# pwm_driver.net
KiCad netlist of a schematic drawn in Altium Designer
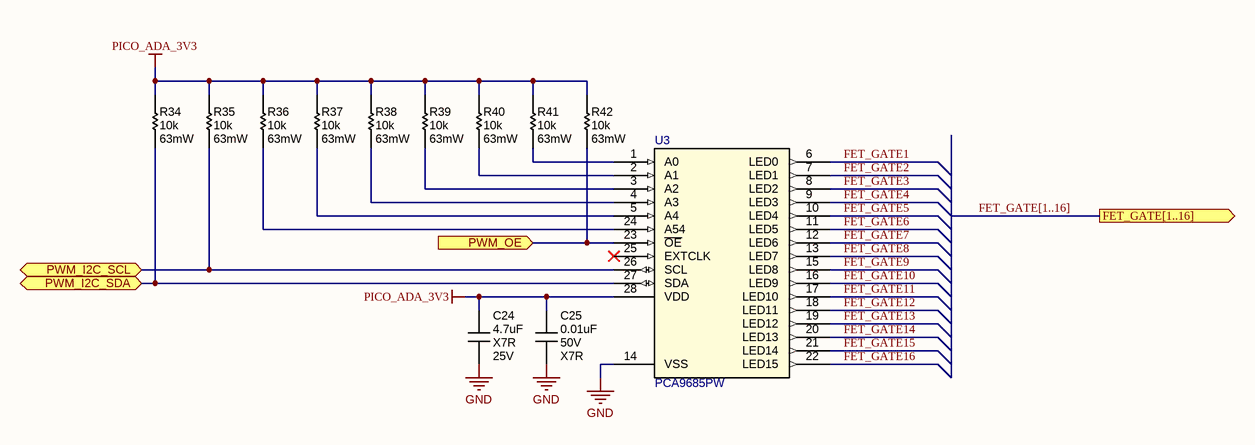
[diagram p0: pwm_driver.SchDoc]

(export (version "E")
  (design (tool "Eeschema 10.0.6"))
  (components
    (comp (ref "C24")
      (value "4.7uF")
      (footprint "CAPC2012X14N")
      (description "CAP CER 4.7UF 25V X7R 0805")
      (fields
        (field (name "MFR") "TDK Corporation")
        (field (name "TOLERANCE") "10%")
        (field (name "TEMP COEFF") "X7R")
        (field (name "VOLTAGE RATING") "25V")
      )
      (libsource (lib "General_Library") (part "CMP-004-0011"))
    )
    (comp (ref "C25")
      (value "0.01uF")
      (footprint "CAPC1005X06N")
      (description "CAP CER SMD 0.01UF 50V X7R 0402")
      (fields
        (field (name "TOLERANCE") "10%")
        (field (name "MFR") "Murata Electronics")
        (field (name "VOLTAGE RATING") "50V")
        (field (name "TEMP COEFF") "X7R")
      )
      (libsource (lib "General_Library") (part "CMP-004-0077"))
    )
    (comp (ref "R34")
      (value "10k")
      (footprint "RESC1005X04N")
      (description "RES SMD 10K OHM 0.5% 1/16W 0402")
      (fields
        (field (name "MFR") "Panasonic Electronic Components")
        (field (name "TOLERANCE") "0.5%")
        (field (name "WATTAGE") "63mW")
      )
      (libsource (lib "General_Library") (part "CMP-025-0026"))
    )
    (comp (ref "R35")
      (value "10k")
      (footprint "RESC1005X04N")
      (description "RES SMD 10K OHM 0.5% 1/16W 0402")
      (fields
        (field (name "MFR") "Panasonic Electronic Components")
        (field (name "TOLERANCE") "0.5%")
        (field (name "WATTAGE") "63mW")
      )
      (libsource (lib "General_Library") (part "CMP-025-0026"))
    )
    (comp (ref "R36")
      (value "10k")
      (footprint "RESC1005X04N")
      (description "RES SMD 10K OHM 0.5% 1/16W 0402")
      (fields
        (field (name "MFR") "Panasonic Electronic Components")
        (field (name "TOLERANCE") "0.5%")
        (field (name "WATTAGE") "63mW")
      )
      (libsource (lib "General_Library") (part "CMP-025-0026"))
    )
    (comp (ref "R37")
      (value "10k")
      (footprint "RESC1005X04N")
      (description "RES SMD 10K OHM 0.5% 1/16W 0402")
      (fields
        (field (name "MFR") "Panasonic Electronic Components")
        (field (name "TOLERANCE") "0.5%")
        (field (name "WATTAGE") "63mW")
      )
      (libsource (lib "General_Library") (part "CMP-025-0026"))
    )
    (comp (ref "R38")
      (value "10k")
      (footprint "RESC1005X04N")
      (description "RES SMD 10K OHM 0.5% 1/16W 0402")
      (fields
        (field (name "MFR") "Panasonic Electronic Components")
        (field (name "TOLERANCE") "0.5%")
        (field (name "WATTAGE") "63mW")
      )
      (libsource (lib "General_Library") (part "CMP-025-0026"))
    )
    (comp (ref "R39")
      (value "10k")
      (footprint "RESC1005X04N")
      (description "RES SMD 10K OHM 0.5% 1/16W 0402")
      (fields
        (field (name "MFR") "Panasonic Electronic Components")
        (field (name "TOLERANCE") "0.5%")
        (field (name "WATTAGE") "63mW")
      )
      (libsource (lib "General_Library") (part "CMP-025-0026"))
    )
    (comp (ref "R40")
      (value "10k")
      (footprint "RESC1005X04N")
      (description "RES SMD 10K OHM 0.5% 1/16W 0402")
      (fields
        (field (name "MFR") "Panasonic Electronic Components")
        (field (name "TOLERANCE") "0.5%")
        (field (name "WATTAGE") "63mW")
      )
      (libsource (lib "General_Library") (part "CMP-025-0026"))
    )
    (comp (ref "R41")
      (value "10k")
      (footprint "RESC1005X04N")
      (description "RES SMD 10K OHM 0.5% 1/16W 0402")
      (fields
        (field (name "MFR") "Panasonic Electronic Components")
        (field (name "TOLERANCE") "0.5%")
        (field (name "WATTAGE") "63mW")
      )
      (libsource (lib "General_Library") (part "CMP-025-0026"))
    )
    (comp (ref "R42")
      (value "10k")
      (footprint "RESC1005X04N")
      (description "RES SMD 10K OHM 0.5% 1/16W 0402")
      (fields
        (field (name "MFR") "Panasonic Electronic Components")
        (field (name "TOLERANCE") "0.5%")
        (field (name "WATTAGE") "63mW")
      )
      (libsource (lib "General_Library") (part "CMP-025-0026"))
    )
    (comp (ref "U3")
      (value "PCA9685PW")
      (footprint "SOP65P640X120-29N")
      (description "IC LED DRVR LIN PWM 25MA 28TSSOP")
      (fields (field (name "MFR") "NXP"))
      (libsource (lib "General_Library") (part "CMP-017-0112"))
    )
  )
  (nets
    (net (code "1") (name "/FET_GATE1") (class "Default")
      (node (ref "U3") (pin "6") (pinfunction "LED0_6") (pintype "output"))
    )
    (net (code "2") (name "/FET_GATE2") (class "Default")
      (node (ref "U3") (pin "7") (pinfunction "LED1_7") (pintype "output"))
    )
    (net (code "3") (name "/FET_GATE3") (class "Default")
      (node (ref "U3") (pin "8") (pinfunction "LED2_8") (pintype "output"))
    )
    (net (code "4") (name "/FET_GATE4") (class "Default")
      (node (ref "U3") (pin "9") (pinfunction "LED3_9") (pintype "output"))
    )
    (net (code "5") (name "/FET_GATE5") (class "Default")
      (node (ref "U3") (pin "10") (pinfunction "LED4_10") (pintype "output"))
    )
    (net (code "6") (name "/FET_GATE6") (class "Default")
      (node (ref "U3") (pin "11") (pinfunction "LED5_11") (pintype "output"))
    )
    (net (code "7") (name "/FET_GATE7") (class "Default")
      (node (ref "U3") (pin "12") (pinfunction "LED6_12") (pintype "output"))
    )
    (net (code "8") (name "/FET_GATE8") (class "Default")
      (node (ref "U3") (pin "13") (pinfunction "LED7_13") (pintype "output"))
    )
    (net (code "9") (name "/FET_GATE9") (class "Default")
      (node (ref "U3") (pin "15") (pinfunction "LED8_15") (pintype "output"))
    )
    (net (code "10") (name "/FET_GATE10") (class "Default")
      (node (ref "U3") (pin "16") (pinfunction "LED9_16") (pintype "output"))
    )
    (net (code "11") (name "/FET_GATE11") (class "Default")
      (node (ref "U3") (pin "17") (pinfunction "LED10_17") (pintype "output"))
    )
    (net (code "12") (name "/FET_GATE12") (class "Default")
      (node (ref "U3") (pin "18") (pinfunction "LED11_18") (pintype "output"))
    )
    (net (code "13") (name "/FET_GATE13") (class "Default")
      (node (ref "U3") (pin "19") (pinfunction "LED12_19") (pintype "output"))
    )
    (net (code "14") (name "/FET_GATE14") (class "Default")
      (node (ref "U3") (pin "20") (pinfunction "LED13_20") (pintype "output"))
    )
    (net (code "15") (name "/FET_GATE15") (class "Default")
      (node (ref "U3") (pin "21") (pinfunction "LED14_21") (pintype "output"))
    )
    (net (code "16") (name "/FET_GATE16") (class "Default")
      (node (ref "U3") (pin "22") (pinfunction "LED15_22") (pintype "output"))
    )
    (net (code "18") (name "/PWM_I2C_SCL") (class "Default")
      (node (ref "R35") (pin "1") (pinfunction "1_1") (pintype "passive"))
      (node (ref "U3") (pin "26") (pinfunction "SCL_26") (pintype "bidirectional"))
    )
    (net (code "19") (name "/PWM_I2C_SDA") (class "Default")
      (node (ref "R34") (pin "1") (pinfunction "1_1") (pintype "passive"))
      (node (ref "U3") (pin "27") (pinfunction "SDA_27") (pintype "bidirectional"))
    )
    (net (code "20") (name "/PWM_OE") (class "Default")
      (node (ref "R42") (pin "1") (pinfunction "1_1") (pintype "passive"))
      (node (ref "U3") (pin "23") (pinfunction "~{OE}_23") (pintype "input"))
    )
    (net (code "21") (name "GND") (class "Default")
      (node (ref "C24") (pin "2") (pinfunction "2_2") (pintype "passive"))
      (node (ref "C25") (pin "2") (pinfunction "2_2") (pintype "passive"))
      (node (ref "U3") (pin "14") (pinfunction "VSS_14") (pintype "power_in"))
    )
    (net (code "22") (name "Net-(U3-A0)") (class "Default")
      (node (ref "R41") (pin "1") (pinfunction "1_1") (pintype "passive"))
      (node (ref "U3") (pin "1") (pinfunction "A0_1") (pintype "input"))
    )
    (net (code "23") (name "Net-(U3-A1)") (class "Default")
      (node (ref "R40") (pin "1") (pinfunction "1_1") (pintype "passive"))
      (node (ref "U3") (pin "2") (pinfunction "A1_2") (pintype "input"))
    )
    (net (code "24") (name "Net-(U3-A2)") (class "Default")
      (node (ref "R39") (pin "1") (pinfunction "1_1") (pintype "passive"))
      (node (ref "U3") (pin "3") (pinfunction "A2_3") (pintype "input"))
    )
    (net (code "25") (name "Net-(U3-A3)") (class "Default")
      (node (ref "R38") (pin "1") (pinfunction "1_1") (pintype "passive"))
      (node (ref "U3") (pin "4") (pinfunction "A3_4") (pintype "input"))
    )
    (net (code "26") (name "Net-(U3-A4)") (class "Default")
      (node (ref "R37") (pin "1") (pinfunction "1_1") (pintype "passive"))
      (node (ref "U3") (pin "5") (pinfunction "A4_5") (pintype "input"))
    )
    (net (code "27") (name "Net-(U3-A54)") (class "Default")
      (node (ref "R36") (pin "1") (pinfunction "1_1") (pintype "passive"))
      (node (ref "U3") (pin "24") (pinfunction "A54_24") (pintype "input"))
    )
    (net (code "28") (name "PICO_ADA_3V3") (class "Default")
      (node (ref "C24") (pin "1") (pinfunction "1_1") (pintype "passive"))
      (node (ref "C25") (pin "1") (pinfunction "1_1") (pintype "passive"))
      (node (ref "R34") (pin "2") (pinfunction "2_2") (pintype "passive"))
      (node (ref "R35") (pin "2") (pinfunction "2_2") (pintype "passive"))
      (node (ref "R36") (pin "2") (pinfunction "2_2") (pintype "passive"))
      (node (ref "R37") (pin "2") (pinfunction "2_2") (pintype "passive"))
      (node (ref "R38") (pin "2") (pinfunction "2_2") (pintype "passive"))
      (node (ref "R39") (pin "2") (pinfunction "2_2") (pintype "passive"))
      (node (ref "R40") (pin "2") (pinfunction "2_2") (pintype "passive"))
      (node (ref "R41") (pin "2") (pinfunction "2_2") (pintype "passive"))
      (node (ref "R42") (pin "2") (pinfunction "2_2") (pintype "passive"))
      (node (ref "U3") (pin "28") (pinfunction "VDD_28") (pintype "power_in"))
    )
    (net (code "29") (name "unconnected-(U3-EXTCLK-Pad25)") (class "Default")
      (node (ref "U3") (pin "25") (pinfunction "EXTCLK_25") (pintype "input+no_connect"))
    )
  )
)
